# SCH_13W3_to_DA15_Apple_Display_Adapter_2.net
KiCad netlist of a schematic drawn in EasyEDA
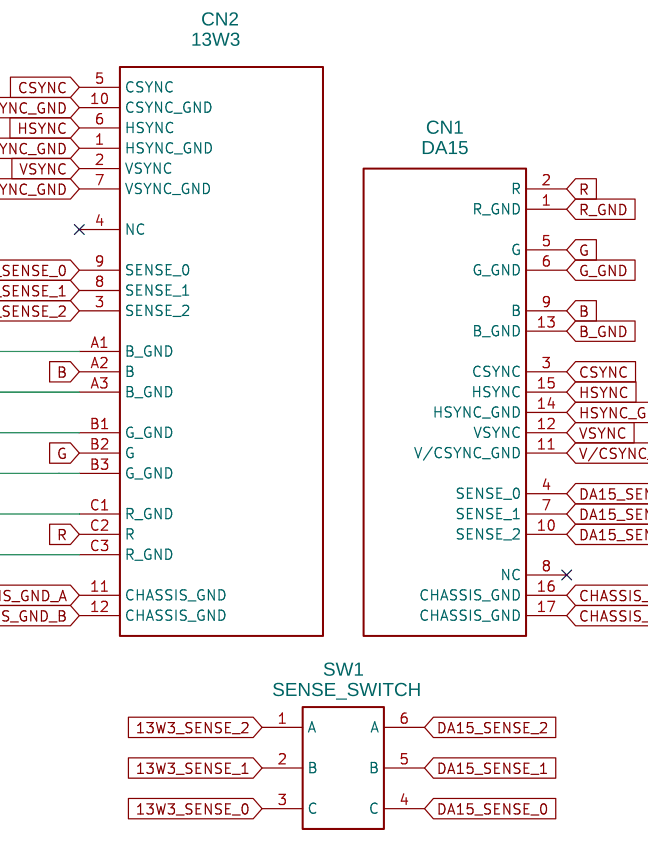
[diagram p0: schematic sheet]

(export (version "E")
  (design (tool "Eeschema 10.0.6"))
  (components
    (comp (ref "CN1") (value "DA15") (libsource (lib "") (part "APPLE_DA15_VIDEO_CONNECTOR_PCB_MOUNT")))
    (comp (ref "CN2") (value "13W3") (libsource (lib "") (part "13W3_APPLE_VIDEO_RIGHT_ANGLE_PCB_MOUNT")))
    (comp (ref "SW1")
      (value "SENSE_SWITCH")
      (fields
        (field (name "BOM_Manufacturer Part") "418117270903")
        (field (name "BOM_Supplier Part") "710-418117270903")
      )
      (libsource (lib "") (part "DIP_SWITCH_3POS"))
    )
  )
  (nets
    (net (code "1") (name "13W3_SENSE_0") (class "Default")
      (node (ref "CN2") (pin "9") (pinfunction "SENSE_0_9") (pintype "unspecified"))
      (node (ref "SW1") (pin "3") (pinfunction "C_3") (pintype "unspecified"))
    )
    (net (code "2") (name "13W3_SENSE_1") (class "Default")
      (node (ref "CN2") (pin "8") (pinfunction "SENSE_1_8") (pintype "unspecified"))
      (node (ref "SW1") (pin "2") (pinfunction "B_2") (pintype "unspecified"))
    )
    (net (code "3") (name "13W3_SENSE_2") (class "Default")
      (node (ref "CN2") (pin "3") (pinfunction "SENSE_2_3") (pintype "unspecified"))
      (node (ref "SW1") (pin "1") (pinfunction "A_1") (pintype "unspecified"))
    )
    (net (code "4") (name "B") (class "Default")
      (node (ref "CN1") (pin "9") (pinfunction "B_9") (pintype "unspecified"))
      (node (ref "CN2") (pin "A2") (pinfunction "B_A2") (pintype "unspecified"))
    )
    (net (code "5") (name "B_GND") (class "Default")
      (node (ref "CN1") (pin "13") (pinfunction "B_GND_13") (pintype "unspecified"))
      (node (ref "CN2") (pin "A1") (pinfunction "B_GND_A1") (pintype "unspecified"))
      (node (ref "CN2") (pin "A3") (pinfunction "B_GND_A3") (pintype "unspecified"))
    )
    (net (code "6") (name "CHASSIS_GND_A") (class "Default")
      (node (ref "CN1") (pin "16") (pinfunction "CHASSIS_GND_16") (pintype "unspecified"))
      (node (ref "CN2") (pin "11") (pinfunction "CHASSIS_GND_11") (pintype "unspecified"))
    )
    (net (code "7") (name "CHASSIS_GND_B") (class "Default")
      (node (ref "CN1") (pin "17") (pinfunction "CHASSIS_GND_17") (pintype "unspecified"))
      (node (ref "CN2") (pin "12") (pinfunction "CHASSIS_GND_12") (pintype "unspecified"))
    )
    (net (code "8") (name "CSYNC") (class "Default")
      (node (ref "CN1") (pin "3") (pinfunction "CSYNC_3") (pintype "unspecified"))
      (node (ref "CN2") (pin "5") (pinfunction "CSYNC_5") (pintype "unspecified"))
    )
    (net (code "9") (name "DA15_SENSE_0") (class "Default")
      (node (ref "CN1") (pin "4") (pinfunction "SENSE_0_4") (pintype "unspecified"))
      (node (ref "SW1") (pin "4") (pinfunction "C_4") (pintype "unspecified"))
    )
    (net (code "10") (name "DA15_SENSE_1") (class "Default")
      (node (ref "CN1") (pin "7") (pinfunction "SENSE_1_7") (pintype "unspecified"))
      (node (ref "SW1") (pin "5") (pinfunction "B_5") (pintype "unspecified"))
    )
    (net (code "11") (name "DA15_SENSE_2") (class "Default")
      (node (ref "CN1") (pin "10") (pinfunction "SENSE_2_10") (pintype "unspecified"))
      (node (ref "SW1") (pin "6") (pinfunction "A_6") (pintype "unspecified"))
    )
    (net (code "12") (name "G") (class "Default")
      (node (ref "CN1") (pin "5") (pinfunction "G_5") (pintype "unspecified"))
      (node (ref "CN2") (pin "B2") (pinfunction "G_B2") (pintype "unspecified"))
    )
    (net (code "13") (name "G_GND") (class "Default")
      (node (ref "CN1") (pin "6") (pinfunction "G_GND_6") (pintype "unspecified"))
      (node (ref "CN2") (pin "B1") (pinfunction "G_GND_B1") (pintype "unspecified"))
      (node (ref "CN2") (pin "B3") (pinfunction "G_GND_B3") (pintype "unspecified"))
    )
    (net (code "14") (name "HSYNC") (class "Default")
      (node (ref "CN1") (pin "15") (pinfunction "HSYNC_15") (pintype "unspecified"))
      (node (ref "CN2") (pin "6") (pinfunction "HSYNC_6") (pintype "unspecified"))
    )
    (net (code "15") (name "HSYNC_GND") (class "Default")
      (node (ref "CN1") (pin "14") (pinfunction "HSYNC_GND_14") (pintype "unspecified"))
      (node (ref "CN2") (pin "1") (pinfunction "HSYNC_GND_1") (pintype "unspecified"))
    )
    (net (code "16") (name "R") (class "Default")
      (node (ref "CN1") (pin "2") (pinfunction "R_2") (pintype "unspecified"))
      (node (ref "CN2") (pin "C2") (pinfunction "R_C2") (pintype "unspecified"))
    )
    (net (code "17") (name "R_GND") (class "Default")
      (node (ref "CN1") (pin "1") (pinfunction "R_GND_1") (pintype "unspecified"))
      (node (ref "CN2") (pin "C1") (pinfunction "R_GND_C1") (pintype "unspecified"))
      (node (ref "CN2") (pin "C3") (pinfunction "R_GND_C3") (pintype "unspecified"))
    )
    (net (code "18") (name "VSYNC") (class "Default")
      (node (ref "CN1") (pin "12") (pinfunction "VSYNC_12") (pintype "unspecified"))
      (node (ref "CN2") (pin "2") (pinfunction "VSYNC_2") (pintype "unspecified"))
    )
    (net (code "19") (name "V{slash}CSYNC_GND") (class "Default")
      (node (ref "CN1") (pin "11") (pinfunction "V/CSYNC_GND_11") (pintype "unspecified"))
      (node (ref "CN2") (pin "10") (pinfunction "CSYNC_GND_10") (pintype "unspecified"))
      (node (ref "CN2") (pin "7") (pinfunction "VSYNC_GND_7") (pintype "unspecified"))
    )
    (net (code "20") (name "unconnected-(CN1-NC-Pad8)") (class "Default")
      (node (ref "CN1") (pin "8") (pinfunction "NC_8") (pintype "unspecified+no_connect"))
    )
    (net (code "21") (name "unconnected-(CN2-NC-Pad4)") (class "Default")
      (node (ref "CN2") (pin "4") (pinfunction "NC_4") (pintype "unspecified+no_connect"))
    )
  )
)
